# JoyStick.net
KiCad netlist of a schematic drawn in Altium Designer
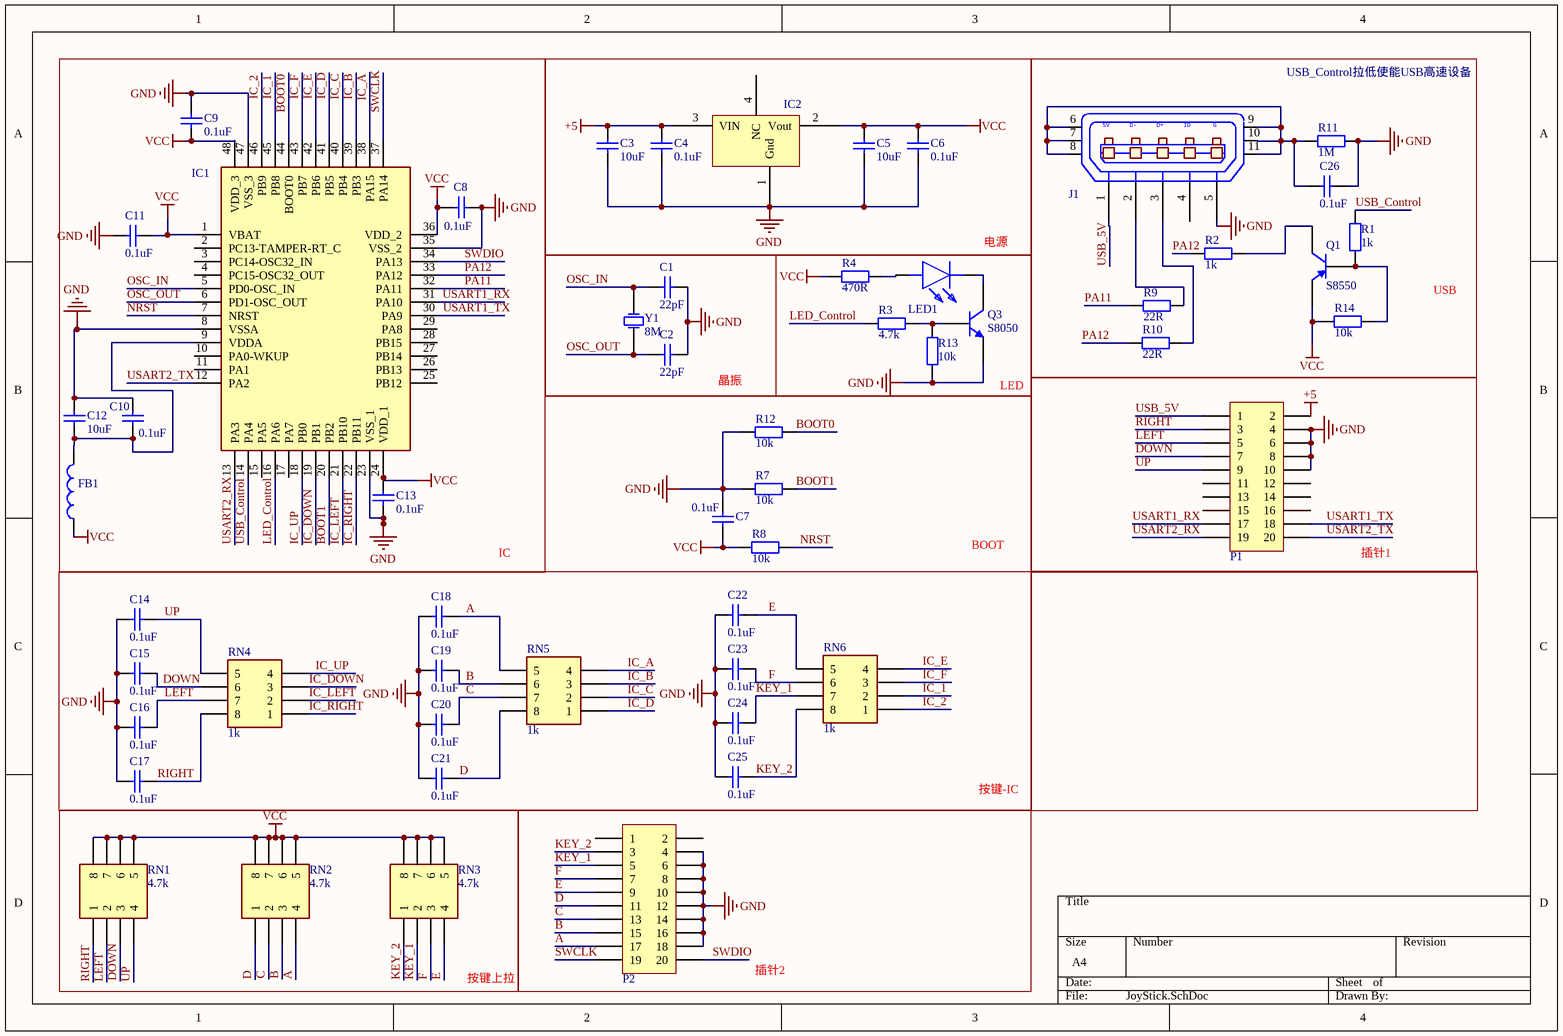
[diagram p0: JoyStick.SchDoc]

(export (version "E")
  (design (tool "Eeschema 10.0.6"))
  (components
    (comp (ref "C1")
      (value "22pF")
      (footprint "CAP-0603")
      (description "Capacitance")
      (libsource (lib "JoyStick") (part "Cap-0603"))
    )
    (comp (ref "C2")
      (value "22pF")
      (footprint "CAP-0603")
      (description "Capacitance")
      (libsource (lib "JoyStick") (part "Cap-0603"))
    )
    (comp (ref "C3")
      (value "10uF")
      (footprint "CAP-1206")
      (description "Capacitance")
      (libsource (lib "JoyStick") (part "Cap-1206"))
    )
    (comp (ref "C4")
      (value "0.1uF")
      (footprint "CAP-0603")
      (description "Capacitance")
      (libsource (lib "JoyStick") (part "Cap-0603"))
    )
    (comp (ref "C5")
      (value "10uF")
      (footprint "CAP-1206")
      (description "Capacitance")
      (libsource (lib "JoyStick") (part "Cap-1206"))
    )
    (comp (ref "C6")
      (value "0.1uF")
      (footprint "CAP-0603")
      (description "Capacitance")
      (libsource (lib "JoyStick") (part "Cap-0603"))
    )
    (comp (ref "C7")
      (value "0.1uF")
      (footprint "CAP-0603")
      (description "Capacitance")
      (libsource (lib "JoyStick") (part "Cap-0603"))
    )
    (comp (ref "C8")
      (value "0.1uF")
      (footprint "CAP-0603")
      (description "Capacitance")
      (libsource (lib "JoyStick") (part "Cap-0603"))
    )
    (comp (ref "C9")
      (value "0.1uF")
      (footprint "CAP-0603")
      (description "Capacitance")
      (libsource (lib "JoyStick") (part "Cap-0603"))
    )
    (comp (ref "C10")
      (value "0.1uF")
      (footprint "CAP-0603")
      (description "Capacitance")
      (libsource (lib "JoyStick") (part "Cap-0603"))
    )
    (comp (ref "C11")
      (value "0.1uF")
      (footprint "CAP-0603")
      (description "Capacitance")
      (libsource (lib "JoyStick") (part "Cap-0603"))
    )
    (comp (ref "C12")
      (value "10uF")
      (footprint "CAP-1206")
      (description "Capacitance")
      (libsource (lib "JoyStick") (part "Cap-1206"))
    )
    (comp (ref "C13")
      (value "0.1uF")
      (footprint "CAP-0603")
      (description "Capacitance")
      (libsource (lib "JoyStick") (part "Cap-0603"))
    )
    (comp (ref "C14")
      (value "0.1uF")
      (footprint "CAP-0603")
      (description "Capacitance")
      (libsource (lib "JoyStick") (part "Cap-0603"))
    )
    (comp (ref "C15")
      (value "0.1uF")
      (footprint "CAP-0603")
      (description "Capacitance")
      (libsource (lib "JoyStick") (part "Cap-0603"))
    )
    (comp (ref "C16")
      (value "0.1uF")
      (footprint "CAP-0603")
      (description "Capacitance")
      (libsource (lib "JoyStick") (part "Cap-0603"))
    )
    (comp (ref "C17")
      (value "0.1uF")
      (footprint "CAP-0603")
      (description "Capacitance")
      (libsource (lib "JoyStick") (part "Cap-0603"))
    )
    (comp (ref "C18")
      (value "0.1uF")
      (footprint "CAP-0603")
      (description "Capacitance")
      (libsource (lib "JoyStick") (part "Cap-0603"))
    )
    (comp (ref "C19")
      (value "0.1uF")
      (footprint "CAP-0603")
      (description "Capacitance")
      (libsource (lib "JoyStick") (part "Cap-0603"))
    )
    (comp (ref "C20")
      (value "0.1uF")
      (footprint "CAP-0603")
      (description "Capacitance")
      (libsource (lib "JoyStick") (part "Cap-0603"))
    )
    (comp (ref "C21")
      (value "0.1uF")
      (footprint "CAP-0603")
      (description "Capacitance")
      (libsource (lib "JoyStick") (part "Cap-0603"))
    )
    (comp (ref "C22")
      (value "0.1uF")
      (footprint "CAP-0603")
      (description "Capacitance")
      (libsource (lib "JoyStick") (part "Cap-0603"))
    )
    (comp (ref "C23")
      (value "0.1uF")
      (footprint "CAP-0603")
      (description "Capacitance")
      (libsource (lib "JoyStick") (part "Cap-0603"))
    )
    (comp (ref "C24")
      (value "0.1uF")
      (footprint "CAP-0603")
      (description "Capacitance")
      (libsource (lib "JoyStick") (part "Cap-0603"))
    )
    (comp (ref "C25")
      (value "0.1uF")
      (footprint "CAP-0603")
      (description "Capacitance")
      (libsource (lib "JoyStick") (part "Cap-0603"))
    )
    (comp (ref "C26")
      (value "0.1uF")
      (footprint "CAP-0603")
      (description "Capacitance")
      (libsource (lib "JoyStick") (part "Cap-0603"))
    )
    (comp (ref "FB1")
      (value "Ferrite Bead")
      (footprint "Ferrite Bead-0603")
      (libsource (lib "JoyStick") (part "Ferrite Bead"))
    )
    (comp (ref "IC1")
      (value "STM32F103C8T6")
      (footprint "LQFP48")
      (description "Integrated Circuit")
      (fields
        (field (name "MANUFACTURER_PART_NUMBER") "STM32F103C8T6TR")
        (field (name "MOUSER PART NUMBER") "511-STM32F103C8T6TR")
      )
      (libsource (lib "JoyStick") (part "STM32F103C8T6"))
    )
    (comp (ref "IC2")
      (value "LM1117MPX-3.3")
      (footprint "SOT-223")
      (description "Integrated Circuit")
      (fields (field (name "MANUFACTURER_PART_NUMBER") "LM1117IMPX3.3/NOPB"))
      (libsource (lib "JoyStick") (part "LM1117MPX-3.3"))
    )
    (comp (ref "J1")
      (value "Micro-USB")
      (footprint "Micro-USB")
      (description "Connector")
      (fields
        (field (name "MANUFACTURER_PART_NUMBER") "10103593-0001LF")
        (field (name "MOUSER PART NUMBER") "649-10103593-0001LF")
      )
      (libsource (lib "JoyStick") (part "Micro-USB"))
    )
    (comp (ref "LED1")
      (value "LED")
      (footprint "LED-0603")
      (fields
        (field (name "MANUFACTURER_PART_NUMBER") "150060SS75020")
        (field (name "MOUSER PART NUMBER") "710-150060SS75020")
      )
      (libsource (lib "JoyStick") (part "LED"))
    )
    (comp (ref "P1")
      (value "Header 10x2")
      (footprint "Header 10x2")
      (libsource (lib "JoyStick") (part "Header 10x2"))
    )
    (comp (ref "P2")
      (value "Header 10x2")
      (footprint "Header 10x2")
      (libsource (lib "JoyStick") (part "Header 10x2"))
    )
    (comp (ref "Q1")
      (value "S8550")
      (footprint "SOT-23")
      (description "PNP")
      (fields (field (name "MANUFACTURER_PART_NUMBER") "S8050G"))
      (libsource (lib "JoyStick") (part "S8550"))
    )
    (comp (ref "Q3")
      (value "S8050")
      (footprint "SOT-23")
      (description "NPN")
      (libsource (lib "JoyStick") (part "S8050"))
    )
    (comp (ref "R1")
      (value "1k")
      (footprint "Res-0603")
      (description "Resistor")
      (libsource (lib "") (part "Res-0603_2"))
    )
    (comp (ref "R2")
      (value "1k")
      (footprint "Res-0603")
      (description "Resistor")
      (libsource (lib "JoyStick") (part "Res-0603"))
    )
    (comp (ref "R3")
      (value "4.7k")
      (footprint "Res-0603")
      (description "Resistor")
      (libsource (lib "JoyStick") (part "Res-0603"))
    )
    (comp (ref "R4")
      (value "470R")
      (footprint "Res-0603")
      (description "Resistor")
      (libsource (lib "JoyStick") (part "Res-0603"))
    )
    (comp (ref "R7")
      (value "10k")
      (footprint "Res-0603")
      (description "Resistor")
      (libsource (lib "JoyStick") (part "Res-0603"))
    )
    (comp (ref "R8")
      (value "10k")
      (footprint "Res-0603")
      (description "Resistor")
      (libsource (lib "JoyStick") (part "Res-0603"))
    )
    (comp (ref "R9")
      (value "22R")
      (footprint "Res-0603")
      (description "Resistor")
      (libsource (lib "JoyStick") (part "Res-0603"))
    )
    (comp (ref "R10")
      (value "22R")
      (footprint "Res-0603")
      (description "Resistor")
      (libsource (lib "JoyStick") (part "Res-0603"))
    )
    (comp (ref "R11")
      (value "1M")
      (footprint "Res-0603")
      (description "Resistor")
      (libsource (lib "JoyStick") (part "Res-0603"))
    )
    (comp (ref "R12")
      (value "10k")
      (footprint "Res-0603")
      (description "Resistor")
      (libsource (lib "JoyStick") (part "Res-0603"))
    )
    (comp (ref "R13")
      (value "10k")
      (footprint "Res-0603")
      (description "Resistor")
      (libsource (lib "") (part "Res-0603_1"))
    )
    (comp (ref "R14")
      (value "10k")
      (footprint "Res-0603")
      (description "Resistor")
      (libsource (lib "") (part "Res-0603_3"))
    )
    (comp (ref "RN1")
      (value "4.7k")
      (footprint "8P4R-0603")
      (description "Resistor Network")
      (fields
        (field (name "MANUFACTURER_PART_NUMBER") "EXB-U38512JV")
        (field (name "MOUSER PART NUMBER") "667-EXB-U38512JV")
      )
      (libsource (lib "JoyStick") (part "8P4R-0603"))
    )
    (comp (ref "RN2")
      (value "4.7k")
      (footprint "8P4R-0603")
      (description "Resistor Network")
      (fields
        (field (name "MANUFACTURER_PART_NUMBER") "EXB-U38512JV")
        (field (name "MOUSER PART NUMBER") "667-EXB-U38512JV")
      )
      (libsource (lib "JoyStick") (part "8P4R-0603"))
    )
    (comp (ref "RN3")
      (value "4.7k")
      (footprint "8P4R-0603")
      (description "Resistor Network")
      (fields
        (field (name "MANUFACTURER_PART_NUMBER") "EXB-U38512JV")
        (field (name "MOUSER PART NUMBER") "667-EXB-U38512JV")
      )
      (libsource (lib "JoyStick") (part "8P4R-0603"))
    )
    (comp (ref "RN4")
      (value "1k")
      (footprint "8P4R-0603")
      (description "Resistor Network")
      (fields
        (field (name "MANUFACTURER_PART_NUMBER") "EXB-U38512JV")
        (field (name "MOUSER PART NUMBER") "667-EXB-U38512JV")
      )
      (libsource (lib "") (part "8P4R-0603_1"))
    )
    (comp (ref "RN5")
      (value "1k")
      (footprint "8P4R-0603")
      (description "Resistor Network")
      (fields
        (field (name "MANUFACTURER_PART_NUMBER") "EXB-U38512JV")
        (field (name "MOUSER PART NUMBER") "667-EXB-U38512JV")
      )
      (libsource (lib "") (part "8P4R-0603_1"))
    )
    (comp (ref "RN6")
      (value "1k")
      (footprint "8P4R-0603")
      (description "Resistor Network")
      (fields
        (field (name "MANUFACTURER_PART_NUMBER") "EXB-U38512JV")
        (field (name "MOUSER PART NUMBER") "667-EXB-U38512JV")
      )
      (libsource (lib "") (part "8P4R-0603_1"))
    )
    (comp (ref "Y1")
      (value "8M")
      (footprint "49-SMD")
      (description "Crystal Oscillator")
      (fields (field (name "MANUFACTURER_PART_NUMBER") "ESB16.0000F12M25F"))
      (libsource (lib "JoyStick") (part "XTAL"))
    )
  )
  (nets
    (net (code "1") (name "+5") (class "Default")
      (node (ref "C3") (pin "2") (pinfunction "2_2") (pintype "passive"))
      (node (ref "C4") (pin "2") (pinfunction "2_2") (pintype "passive"))
      (node (ref "IC2") (pin "3") (pinfunction "VIN_3") (pintype "passive"))
      (node (ref "P1") (pin "2") (pinfunction "2_2") (pintype "passive"))
    )
    (net (code "2") (name "/A") (class "Default")
      (node (ref "C18") (pin "1") (pinfunction "1_1") (pintype "passive"))
      (node (ref "P2") (pin "17") (pinfunction "17_17") (pintype "passive"))
      (node (ref "RN2") (pin "4") (pinfunction "4_4") (pintype "passive"))
      (node (ref "RN5") (pin "5") (pinfunction "5_5") (pintype "passive"))
    )
    (net (code "3") (name "/B") (class "Default")
      (node (ref "C19") (pin "1") (pinfunction "1_1") (pintype "passive"))
      (node (ref "P2") (pin "15") (pinfunction "15_15") (pintype "passive"))
      (node (ref "RN2") (pin "3") (pinfunction "3_3") (pintype "passive"))
      (node (ref "RN5") (pin "6") (pinfunction "6_6") (pintype "passive"))
    )
    (net (code "4") (name "/BOOT0") (class "Default")
      (node (ref "IC1") (pin "44") (pinfunction "BOOT0_44") (pintype "passive"))
      (node (ref "R12") (pin "2") (pinfunction "2_2") (pintype "passive"))
    )
    (net (code "5") (name "/BOOT1") (class "Default")
      (node (ref "IC1") (pin "20") (pinfunction "PB2_20") (pintype "passive"))
      (node (ref "R7") (pin "2") (pinfunction "2_2") (pintype "passive"))
    )
    (net (code "6") (name "/C") (class "Default")
      (node (ref "C20") (pin "1") (pinfunction "1_1") (pintype "passive"))
      (node (ref "P2") (pin "13") (pinfunction "13_13") (pintype "passive"))
      (node (ref "RN2") (pin "2") (pinfunction "2_2") (pintype "passive"))
      (node (ref "RN5") (pin "7") (pinfunction "7_7") (pintype "passive"))
    )
    (net (code "7") (name "/D") (class "Default")
      (node (ref "C21") (pin "1") (pinfunction "1_1") (pintype "passive"))
      (node (ref "P2") (pin "11") (pinfunction "11_11") (pintype "passive"))
      (node (ref "RN2") (pin "1") (pinfunction "1_1") (pintype "passive"))
      (node (ref "RN5") (pin "8") (pinfunction "8_8") (pintype "passive"))
    )
    (net (code "8") (name "/DOWN") (class "Default")
      (node (ref "C15") (pin "1") (pinfunction "1_1") (pintype "passive"))
      (node (ref "P1") (pin "7") (pinfunction "7_7") (pintype "passive"))
      (node (ref "RN1") (pin "3") (pinfunction "3_3") (pintype "passive"))
      (node (ref "RN4") (pin "6") (pinfunction "6_6") (pintype "passive"))
    )
    (net (code "9") (name "/E") (class "Default")
      (node (ref "C22") (pin "1") (pinfunction "1_1") (pintype "passive"))
      (node (ref "P2") (pin "9") (pinfunction "9_9") (pintype "passive"))
      (node (ref "RN3") (pin "4") (pinfunction "4_4") (pintype "passive"))
      (node (ref "RN6") (pin "5") (pinfunction "5_5") (pintype "passive"))
    )
    (net (code "10") (name "/F") (class "Default")
      (node (ref "C23") (pin "1") (pinfunction "1_1") (pintype "passive"))
      (node (ref "P2") (pin "7") (pinfunction "7_7") (pintype "passive"))
      (node (ref "RN3") (pin "3") (pinfunction "3_3") (pintype "passive"))
      (node (ref "RN6") (pin "6") (pinfunction "6_6") (pintype "passive"))
    )
    (net (code "11") (name "/IC_1") (class "Default")
      (node (ref "IC1") (pin "45") (pinfunction "PB8_45") (pintype "passive"))
      (node (ref "RN6") (pin "2") (pinfunction "2_2") (pintype "passive"))
    )
    (net (code "12") (name "/IC_2") (class "Default")
      (node (ref "IC1") (pin "46") (pinfunction "PB9_46") (pintype "passive"))
      (node (ref "RN6") (pin "1") (pinfunction "1_1") (pintype "passive"))
    )
    (net (code "13") (name "/IC_A") (class "Default")
      (node (ref "IC1") (pin "38") (pinfunction "PA15_38") (pintype "passive"))
      (node (ref "RN5") (pin "4") (pinfunction "4_4") (pintype "passive"))
    )
    (net (code "14") (name "/IC_B") (class "Default")
      (node (ref "IC1") (pin "39") (pinfunction "PB3_39") (pintype "passive"))
      (node (ref "RN5") (pin "3") (pinfunction "3_3") (pintype "passive"))
    )
    (net (code "15") (name "/IC_C") (class "Default")
      (node (ref "IC1") (pin "40") (pinfunction "PB4_40") (pintype "passive"))
      (node (ref "RN5") (pin "2") (pinfunction "2_2") (pintype "passive"))
    )
    (net (code "16") (name "/IC_D") (class "Default")
      (node (ref "IC1") (pin "41") (pinfunction "PB5_41") (pintype "passive"))
      (node (ref "RN5") (pin "1") (pinfunction "1_1") (pintype "passive"))
    )
    (net (code "17") (name "/IC_DOWN") (class "Default")
      (node (ref "IC1") (pin "19") (pinfunction "PB1_19") (pintype "passive"))
      (node (ref "RN4") (pin "3") (pinfunction "3_3") (pintype "passive"))
    )
    (net (code "18") (name "/IC_E") (class "Default")
      (node (ref "IC1") (pin "42") (pinfunction "PB6_42") (pintype "passive"))
      (node (ref "RN6") (pin "4") (pinfunction "4_4") (pintype "passive"))
    )
    (net (code "19") (name "/IC_F") (class "Default")
      (node (ref "IC1") (pin "43") (pinfunction "PB7_43") (pintype "passive"))
      (node (ref "RN6") (pin "3") (pinfunction "3_3") (pintype "passive"))
    )
    (net (code "20") (name "/IC_LEFT") (class "Default")
      (node (ref "IC1") (pin "21") (pinfunction "PB10_21") (pintype "passive"))
      (node (ref "RN4") (pin "2") (pinfunction "2_2") (pintype "passive"))
    )
    (net (code "21") (name "/IC_RIGHT") (class "Default")
      (node (ref "IC1") (pin "22") (pinfunction "PB11_22") (pintype "passive"))
      (node (ref "RN4") (pin "1") (pinfunction "1_1") (pintype "passive"))
    )
    (net (code "22") (name "/IC_UP") (class "Default")
      (node (ref "IC1") (pin "18") (pinfunction "PB0_18") (pintype "passive"))
      (node (ref "RN4") (pin "4") (pinfunction "4_4") (pintype "passive"))
    )
    (net (code "23") (name "/KEY_1") (class "Default")
      (node (ref "C24") (pin "1") (pinfunction "1_1") (pintype "passive"))
      (node (ref "P2") (pin "5") (pinfunction "5_5") (pintype "passive"))
      (node (ref "RN3") (pin "2") (pinfunction "2_2") (pintype "passive"))
      (node (ref "RN6") (pin "7") (pinfunction "7_7") (pintype "passive"))
    )
    (net (code "24") (name "/KEY_2") (class "Default")
      (node (ref "C25") (pin "1") (pinfunction "1_1") (pintype "passive"))
      (node (ref "P2") (pin "3") (pinfunction "3_3") (pintype "passive"))
      (node (ref "RN3") (pin "1") (pinfunction "1_1") (pintype "passive"))
      (node (ref "RN6") (pin "8") (pinfunction "8_8") (pintype "passive"))
    )
    (net (code "25") (name "/LED_Control") (class "Default")
      (node (ref "IC1") (pin "16") (pinfunction "PA6_16") (pintype "passive"))
      (node (ref "R3") (pin "1") (pinfunction "1_1") (pintype "passive"))
    )
    (net (code "26") (name "/LEFT") (class "Default")
      (node (ref "C16") (pin "1") (pinfunction "1_1") (pintype "passive"))
      (node (ref "P1") (pin "5") (pinfunction "5_5") (pintype "passive"))
      (node (ref "RN1") (pin "2") (pinfunction "2_2") (pintype "passive"))
      (node (ref "RN4") (pin "7") (pinfunction "7_7") (pintype "passive"))
    )
    (net (code "27") (name "/NRST") (class "Default")
      (node (ref "IC1") (pin "7") (pinfunction "NRST_7") (pintype "passive"))
      (node (ref "R8") (pin "2") (pinfunction "2_2") (pintype "passive"))
    )
    (net (code "28") (name "/OSC_IN") (class "Default")
      (node (ref "C1") (pin "1") (pinfunction "1_1") (pintype "passive"))
      (node (ref "IC1") (pin "5") (pinfunction "PD0-OSC_IN_5") (pintype "passive"))
      (node (ref "Y1") (pin "2") (pinfunction "OSC2_2") (pintype "passive"))
    )
    (net (code "29") (name "/OSC_OUT") (class "Default")
      (node (ref "C2") (pin "1") (pinfunction "1_1") (pintype "passive"))
      (node (ref "IC1") (pin "6") (pinfunction "PD1-OSC_OUT_6") (pintype "passive"))
      (node (ref "Y1") (pin "1") (pinfunction "OSC1_1") (pintype "passive"))
    )
    (net (code "30") (name "/PA11") (class "Default")
      (node (ref "IC1") (pin "32") (pinfunction "PA11_32") (pintype "passive"))
      (node (ref "R9") (pin "1") (pinfunction "1_1") (pintype "passive"))
    )
    (net (code "31") (name "/PA12") (class "Default")
      (node (ref "IC1") (pin "33") (pinfunction "PA12_33") (pintype "passive"))
      (node (ref "R10") (pin "1") (pinfunction "1_1") (pintype "passive"))
      (node (ref "R2") (pin "1") (pinfunction "1_1") (pintype "passive"))
    )
    (net (code "32") (name "/RIGHT") (class "Default")
      (node (ref "C17") (pin "1") (pinfunction "1_1") (pintype "passive"))
      (node (ref "P1") (pin "3") (pinfunction "3_3") (pintype "passive"))
      (node (ref "RN1") (pin "1") (pinfunction "1_1") (pintype "passive"))
      (node (ref "RN4") (pin "8") (pinfunction "8_8") (pintype "passive"))
    )
    (net (code "33") (name "/SWCLK") (class "Default")
      (node (ref "IC1") (pin "37") (pinfunction "PA14_37") (pintype "passive"))
      (node (ref "P2") (pin "19") (pinfunction "19_19") (pintype "passive"))
    )
    (net (code "34") (name "/SWDIO") (class "Default")
      (node (ref "IC1") (pin "34") (pinfunction "PA13_34") (pintype "passive"))
      (node (ref "P2") (pin "20") (pinfunction "20_20") (pintype "passive"))
    )
    (net (code "35") (name "/UP") (class "Default")
      (node (ref "C14") (pin "1") (pinfunction "1_1") (pintype "passive"))
      (node (ref "P1") (pin "9") (pinfunction "9_9") (pintype "passive"))
      (node (ref "RN1") (pin "4") (pinfunction "4_4") (pintype "passive"))
      (node (ref "RN4") (pin "5") (pinfunction "5_5") (pintype "passive"))
    )
    (net (code "36") (name "/USART1_RX") (class "Default")
      (node (ref "IC1") (pin "31") (pinfunction "PA10_31") (pintype "passive"))
      (node (ref "P1") (pin "17") (pinfunction "17_17") (pintype "passive"))
    )
    (net (code "37") (name "/USART1_TX") (class "Default")
      (node (ref "IC1") (pin "30") (pinfunction "PA9_30") (pintype "passive"))
      (node (ref "P1") (pin "18") (pinfunction "18_18") (pintype "passive"))
    )
    (net (code "38") (name "/USART2_RX") (class "Default")
      (node (ref "IC1") (pin "13") (pinfunction "PA3_13") (pintype "passive"))
      (node (ref "P1") (pin "19") (pinfunction "19_19") (pintype "passive"))
    )
    (net (code "39") (name "/USART2_TX") (class "Default")
      (node (ref "IC1") (pin "12") (pinfunction "PA2_12") (pintype "passive"))
      (node (ref "P1") (pin "20") (pinfunction "20_20") (pintype "passive"))
    )
    (net (code "40") (name "/USB_5V") (class "Default")
      (node (ref "J1") (pin "1") (pinfunction "P1_1") (pintype "passive"))
      (node (ref "P1") (pin "1") (pinfunction "1_1") (pintype "passive"))
    )
    (net (code "41") (name "/USB_Control") (class "Default")
      (node (ref "IC1") (pin "14") (pinfunction "PA4_14") (pintype "passive"))
      (node (ref "R1") (pin "2") (pinfunction "2_2") (pintype "passive"))
    )
    (net (code "42") (name "GND") (class "Default")
      (node (ref "C1") (pin "2") (pinfunction "2_2") (pintype "passive"))
      (node (ref "C10") (pin "2") (pinfunction "2_2") (pintype "passive"))
      (node (ref "C11") (pin "2") (pinfunction "2_2") (pintype "passive"))
      (node (ref "C12") (pin "2") (pinfunction "2_2") (pintype "passive"))
      (node (ref "C13") (pin "1") (pinfunction "1_1") (pintype "passive"))
      (node (ref "C14") (pin "2") (pinfunction "2_2") (pintype "passive"))
      (node (ref "C15") (pin "2") (pinfunction "2_2") (pintype "passive"))
      (node (ref "C16") (pin "2") (pinfunction "2_2") (pintype "passive"))
      (node (ref "C17") (pin "2") (pinfunction "2_2") (pintype "passive"))
      (node (ref "C18") (pin "2") (pinfunction "2_2") (pintype "passive"))
      (node (ref "C19") (pin "2") (pinfunction "2_2") (pintype "passive"))
      (node (ref "C2") (pin "2") (pinfunction "2_2") (pintype "passive"))
      (node (ref "C20") (pin "2") (pinfunction "2_2") (pintype "passive"))
      (node (ref "C21") (pin "2") (pinfunction "2_2") (pintype "passive"))
      (node (ref "C22") (pin "2") (pinfunction "2_2") (pintype "passive"))
      (node (ref "C23") (pin "2") (pinfunction "2_2") (pintype "passive"))
      (node (ref "C24") (pin "2") (pinfunction "2_2") (pintype "passive"))
      (node (ref "C25") (pin "2") (pinfunction "2_2") (pintype "passive"))
      (node (ref "C26") (pin "1") (pinfunction "1_1") (pintype "passive"))
      (node (ref "C3") (pin "1") (pinfunction "1_1") (pintype "passive"))
      (node (ref "C4") (pin "1") (pinfunction "1_1") (pintype "passive"))
      (node (ref "C5") (pin "1") (pinfunction "1_1") (pintype "passive"))
      (node (ref "C6") (pin "1") (pinfunction "1_1") (pintype "passive"))
      (node (ref "C7") (pin "2") (pinfunction "2_2") (pintype "passive"))
      (node (ref "C8") (pin "1") (pinfunction "1_1") (pintype "passive"))
      (node (ref "C9") (pin "2") (pinfunction "2_2") (pintype "passive"))
      (node (ref "IC1") (pin "23") (pinfunction "VSS_1_23") (pintype "passive"))
      (node (ref "IC1") (pin "35") (pinfunction "VSS_2_35") (pintype "passive"))
      (node (ref "IC1") (pin "47") (pinfunction "VSS_3_47") (pintype "passive"))
      (node (ref "IC1") (pin "8") (pinfunction "VSSA_8") (pintype "passive"))
      (node (ref "IC2") (pin "1") (pinfunction "Gnd_1") (pintype "passive"))
      (node (ref "J1") (pin "5") (pinfunction "P5_5") (pintype "passive"))
      (node (ref "P1") (pin "10") (pinfunction "10_10") (pintype "passive"))
      (node (ref "P1") (pin "4") (pinfunction "4_4") (pintype "passive"))
      (node (ref "P1") (pin "6") (pinfunction "6_6") (pintype "passive"))
      (node (ref "P1") (pin "8") (pinfunction "8_8") (pintype "passive"))
      (node (ref "P2") (pin "10") (pinfunction "10_10") (pintype "passive"))
      (node (ref "P2") (pin "12") (pinfunction "12_12") (pintype "passive"))
      (node (ref "P2") (pin "14") (pinfunction "14_14") (pintype "passive"))
      (node (ref "P2") (pin "16") (pinfunction "16_16") (pintype "passive"))
      (node (ref "P2") (pin "18") (pinfunction "18_18") (pintype "passive"))
      (node (ref "P2") (pin "4") (pinfunction "4_4") (pintype "passive"))
      (node (ref "P2") (pin "6") (pinfunction "6_6") (pintype "passive"))
      (node (ref "P2") (pin "8") (pinfunction "8_8") (pintype "passive"))
      (node (ref "Q3") (pin "2") (pinfunction "E_2") (pintype "passive"))
      (node (ref "R11") (pin "2") (pinfunction "2_2") (pintype "passive"))
      (node (ref "R12") (pin "1") (pinfunction "1_1") (pintype "passive"))
      (node (ref "R13") (pin "2") (pinfunction "2_2") (pintype "passive"))
      (node (ref "R7") (pin "1") (pinfunction "1_1") (pintype "passive"))
    )
    (net (code "43") (name "Net-(IC1-VDDA)") (class "Default")
      (node (ref "C10") (pin "1") (pinfunction "1_1") (pintype "passive"))
      (node (ref "C12") (pin "1") (pinfunction "1_1") (pintype "passive"))
      (node (ref "FB1") (pin "2") (pinfunction "2_2") (pintype "passive"))
      (node (ref "IC1") (pin "9") (pinfunction "VDDA_9") (pintype "passive"))
    )
    (net (code "44") (name "Net-(J1-P2)") (class "Default")
      (node (ref "J1") (pin "2") (pinfunction "P2_2") (pintype "passive"))
      (node (ref "R9") (pin "2") (pinfunction "2_2") (pintype "passive"))
    )
    (net (code "45") (name "Net-(J1-P3)") (class "Default")
      (node (ref "J1") (pin "3") (pinfunction "P3_3") (pintype "passive"))
      (node (ref "R10") (pin "2") (pinfunction "2_2") (pintype "passive"))
    )
    (net (code "46") (name "Net-(J1-SHLD1)") (class "Default")
      (node (ref "C26") (pin "2") (pinfunction "2_2") (pintype "passive"))
      (node (ref "J1") (pin "10") (pinfunction "SHLD5_10") (pintype "passive"))
      (node (ref "J1") (pin "11") (pinfunction "SHLD6_11") (pintype "passive"))
      (node (ref "J1") (pin "6") (pinfunction "SHLD1_6") (pintype "passive"))
      (node (ref "J1") (pin "7") (pinfunction "SHLD2_7") (pintype "passive"))
      (node (ref "J1") (pin "8") (pinfunction "SHLD3_8") (pintype "passive"))
      (node (ref "J1") (pin "9") (pinfunction "SHLD4_9") (pintype "passive"))
      (node (ref "R11") (pin "1") (pinfunction "1_1") (pintype "passive"))
    )
    (net (code "47") (name "Net-(LED1-A)") (class "Default")
      (node (ref "LED1") (pin "1") (pinfunction "A_1") (pintype "passive"))
      (node (ref "R4") (pin "2") (pinfunction "2_2") (pintype "passive"))
    )
    (net (code "48") (name "Net-(LED1-K)") (class "Default")
      (node (ref "LED1") (pin "2") (pinfunction "K_2") (pintype "passive"))
      (node (ref "Q3") (pin "3") (pinfunction "C_3") (pintype "passive"))
    )
    (net (code "49") (name "Net-(Q1-B)") (class "Default")
      (node (ref "Q1") (pin "1") (pinfunction "B_1") (pintype "passive"))
      (node (ref "R1") (pin "1") (pinfunction "1_1") (pintype "passive"))
      (node (ref "R14") (pin "1") (pinfunction "1_1") (pintype "passive"))
    )
    (net (code "50") (name "Net-(Q1-C)") (class "Default")
      (node (ref "Q1") (pin "3") (pinfunction "C_3") (pintype "passive"))
      (node (ref "R2") (pin "2") (pinfunction "2_2") (pintype "passive"))
    )
    (net (code "51") (name "Net-(Q3-B)") (class "Default")
      (node (ref "Q3") (pin "1") (pinfunction "B_1") (pintype "passive"))
      (node (ref "R13") (pin "1") (pinfunction "1_1") (pintype "passive"))
      (node (ref "R3") (pin "2") (pinfunction "2_2") (pintype "passive"))
    )
    (net (code "52") (name "VCC") (class "Default")
      (node (ref "C11") (pin "1") (pinfunction "1_1") (pintype "passive"))
      (node (ref "C13") (pin "2") (pinfunction "2_2") (pintype "passive"))
      (node (ref "C5") (pin "2") (pinfunction "2_2") (pintype "passive"))
      (node (ref "C6") (pin "2") (pinfunction "2_2") (pintype "passive"))
      (node (ref "C7") (pin "1") (pinfunction "1_1") (pintype "passive"))
      (node (ref "C8") (pin "2") (pinfunction "2_2") (pintype "passive"))
      (node (ref "C9") (pin "1") (pinfunction "1_1") (pintype "passive"))
      (node (ref "FB1") (pin "1") (pinfunction "1_1") (pintype "passive"))
      (node (ref "IC1") (pin "1") (pinfunction "VBAT_1") (pintype "passive"))
      (node (ref "IC1") (pin "24") (pinfunction "VDD_1_24") (pintype "passive"))
      (node (ref "IC1") (pin "36") (pinfunction "VDD_2_36") (pintype "passive"))
      (node (ref "IC1") (pin "48") (pinfunction "VDD_3_48") (pintype "passive"))
      (node (ref "IC2") (pin "2") (pinfunction "Vout_2") (pintype "passive"))
      (node (ref "Q1") (pin "2") (pinfunction "E_2") (pintype "passive"))
      (node (ref "R14") (pin "2") (pinfunction "2_2") (pintype "passive"))
      (node (ref "R4") (pin "1") (pinfunction "1_1") (pintype "passive"))
      (node (ref "R8") (pin "1") (pinfunction "1_1") (pintype "passive"))
      (node (ref "RN1") (pin "5") (pinfunction "5_5") (pintype "passive"))
      (node (ref "RN1") (pin "6") (pinfunction "6_6") (pintype "passive"))
      (node (ref "RN1") (pin "7") (pinfunction "7_7") (pintype "passive"))
      (node (ref "RN1") (pin "8") (pinfunction "8_8") (pintype "passive"))
      (node (ref "RN2") (pin "5") (pinfunction "5_5") (pintype "passive"))
      (node (ref "RN2") (pin "6") (pinfunction "6_6") (pintype "passive"))
      (node (ref "RN2") (pin "7") (pinfunction "7_7") (pintype "passive"))
      (node (ref "RN2") (pin "8") (pinfunction "8_8") (pintype "passive"))
      (node (ref "RN3") (pin "5") (pinfunction "5_5") (pintype "passive"))
      (node (ref "RN3") (pin "6") (pinfunction "6_6") (pintype "passive"))
      (node (ref "RN3") (pin "7") (pinfunction "7_7") (pintype "passive"))
      (node (ref "RN3") (pin "8") (pinfunction "8_8") (pintype "passive"))
    )
    (net (code "53") (name "unconnected-(IC1-PA0-WKUP-Pad10)") (class "Default")
      (node (ref "IC1") (pin "10") (pinfunction "PA0-WKUP_10") (pintype "passive"))
    )
    (net (code "54") (name "unconnected-(IC1-PA1-Pad11)") (class "Default")
      (node (ref "IC1") (pin "11") (pinfunction "PA1_11") (pintype "passive"))
    )
    (net (code "55") (name "unconnected-(IC1-PA5-Pad15)") (class "Default")
      (node (ref "IC1") (pin "15") (pinfunction "PA5_15") (pintype "passive"))
    )
    (net (code "56") (name "unconnected-(IC1-PA7-Pad17)") (class "Default")
      (node (ref "IC1") (pin "17") (pinfunction "PA7_17") (pintype "passive"))
    )
    (net (code "57") (name "unconnected-(IC1-PA8-Pad29)") (class "Default")
      (node (ref "IC1") (pin "29") (pinfunction "PA8_29") (pintype "passive"))
    )
    (net (code "58") (name "unconnected-(IC1-PB12-Pad25)") (class "Default")
      (node (ref "IC1") (pin "25") (pinfunction "PB12_25") (pintype "passive"))
    )
    (net (code "59") (name "unconnected-(IC1-PB13-Pad26)") (class "Default")
      (node (ref "IC1") (pin "26") (pinfunction "PB13_26") (pintype "passive"))
    )
    (net (code "60") (name "unconnected-(IC1-PB14-Pad27)") (class "Default")
      (node (ref "IC1") (pin "27") (pinfunction "PB14_27") (pintype "passive"))
    )
    (net (code "61") (name "unconnected-(IC1-PB15-Pad28)") (class "Default")
      (node (ref "IC1") (pin "28") (pinfunction "PB15_28") (pintype "passive"))
    )
    (net (code "62") (name "unconnected-(IC1-PC13-TAMPER-RT_C-Pad2)") (class "Default")
      (node (ref "IC1") (pin "2") (pinfunction "PC13-TAMPER-RT_C_2") (pintype "passive"))
    )
    (net (code "63") (name "unconnected-(IC1-PC14-OSC32_IN-Pad3)") (class "Default")
      (node (ref "IC1") (pin "3") (pinfunction "PC14-OSC32_IN_3") (pintype "passive"))
    )
    (net (code "64") (name "unconnected-(IC1-PC15-OSC32_OUT-Pad4)") (class "Default")
      (node (ref "IC1") (pin "4") (pinfunction "PC15-OSC32_OUT_4") (pintype "passive"))
    )
    (net (code "65") (name "unconnected-(IC2-NC-Pad4)") (class "Default")
      (node (ref "IC2") (pin "4") (pinfunction "NC_4") (pintype "passive"))
    )
    (net (code "66") (name "unconnected-(J1-P4-Pad4)") (class "Default")
      (node (ref "J1") (pin "4") (pinfunction "P4_4") (pintype "passive"))
    )
    (net (code "67") (name "unconnected-(P1-Pad11)") (class "Default")
      (node (ref "P1") (pin "11") (pinfunction "11_11") (pintype "passive"))
    )
    (net (code "68") (name "unconnected-(P1-Pad12)") (class "Default")
      (node (ref "P1") (pin "12") (pinfunction "12_12") (pintype "passive"))
    )
    (net (code "69") (name "unconnected-(P1-Pad13)") (class "Default")
      (node (ref "P1") (pin "13") (pinfunction "13_13") (pintype "passive"))
    )
    (net (code "70") (name "unconnected-(P1-Pad14)") (class "Default")
      (node (ref "P1") (pin "14") (pinfunction "14_14") (pintype "passive"))
    )
    (net (code "71") (name "unconnected-(P1-Pad15)") (class "Default")
      (node (ref "P1") (pin "15") (pinfunction "15_15") (pintype "passive"))
    )
    (net (code "72") (name "unconnected-(P1-Pad16)") (class "Default")
      (node (ref "P1") (pin "16") (pinfunction "16_16") (pintype "passive"))
    )
    (net (code "73") (name "unconnected-(P2-Pad1)") (class "Default")
      (node (ref "P2") (pin "1") (pinfunction "1_1") (pintype "passive"))
    )
    (net (code "74") (name "unconnected-(P2-Pad2)") (class "Default")
      (node (ref "P2") (pin "2") (pinfunction "2_2") (pintype "passive"))
    )
  )
)
